# MCU.net
KiCad netlist of a schematic drawn in Altium Designer
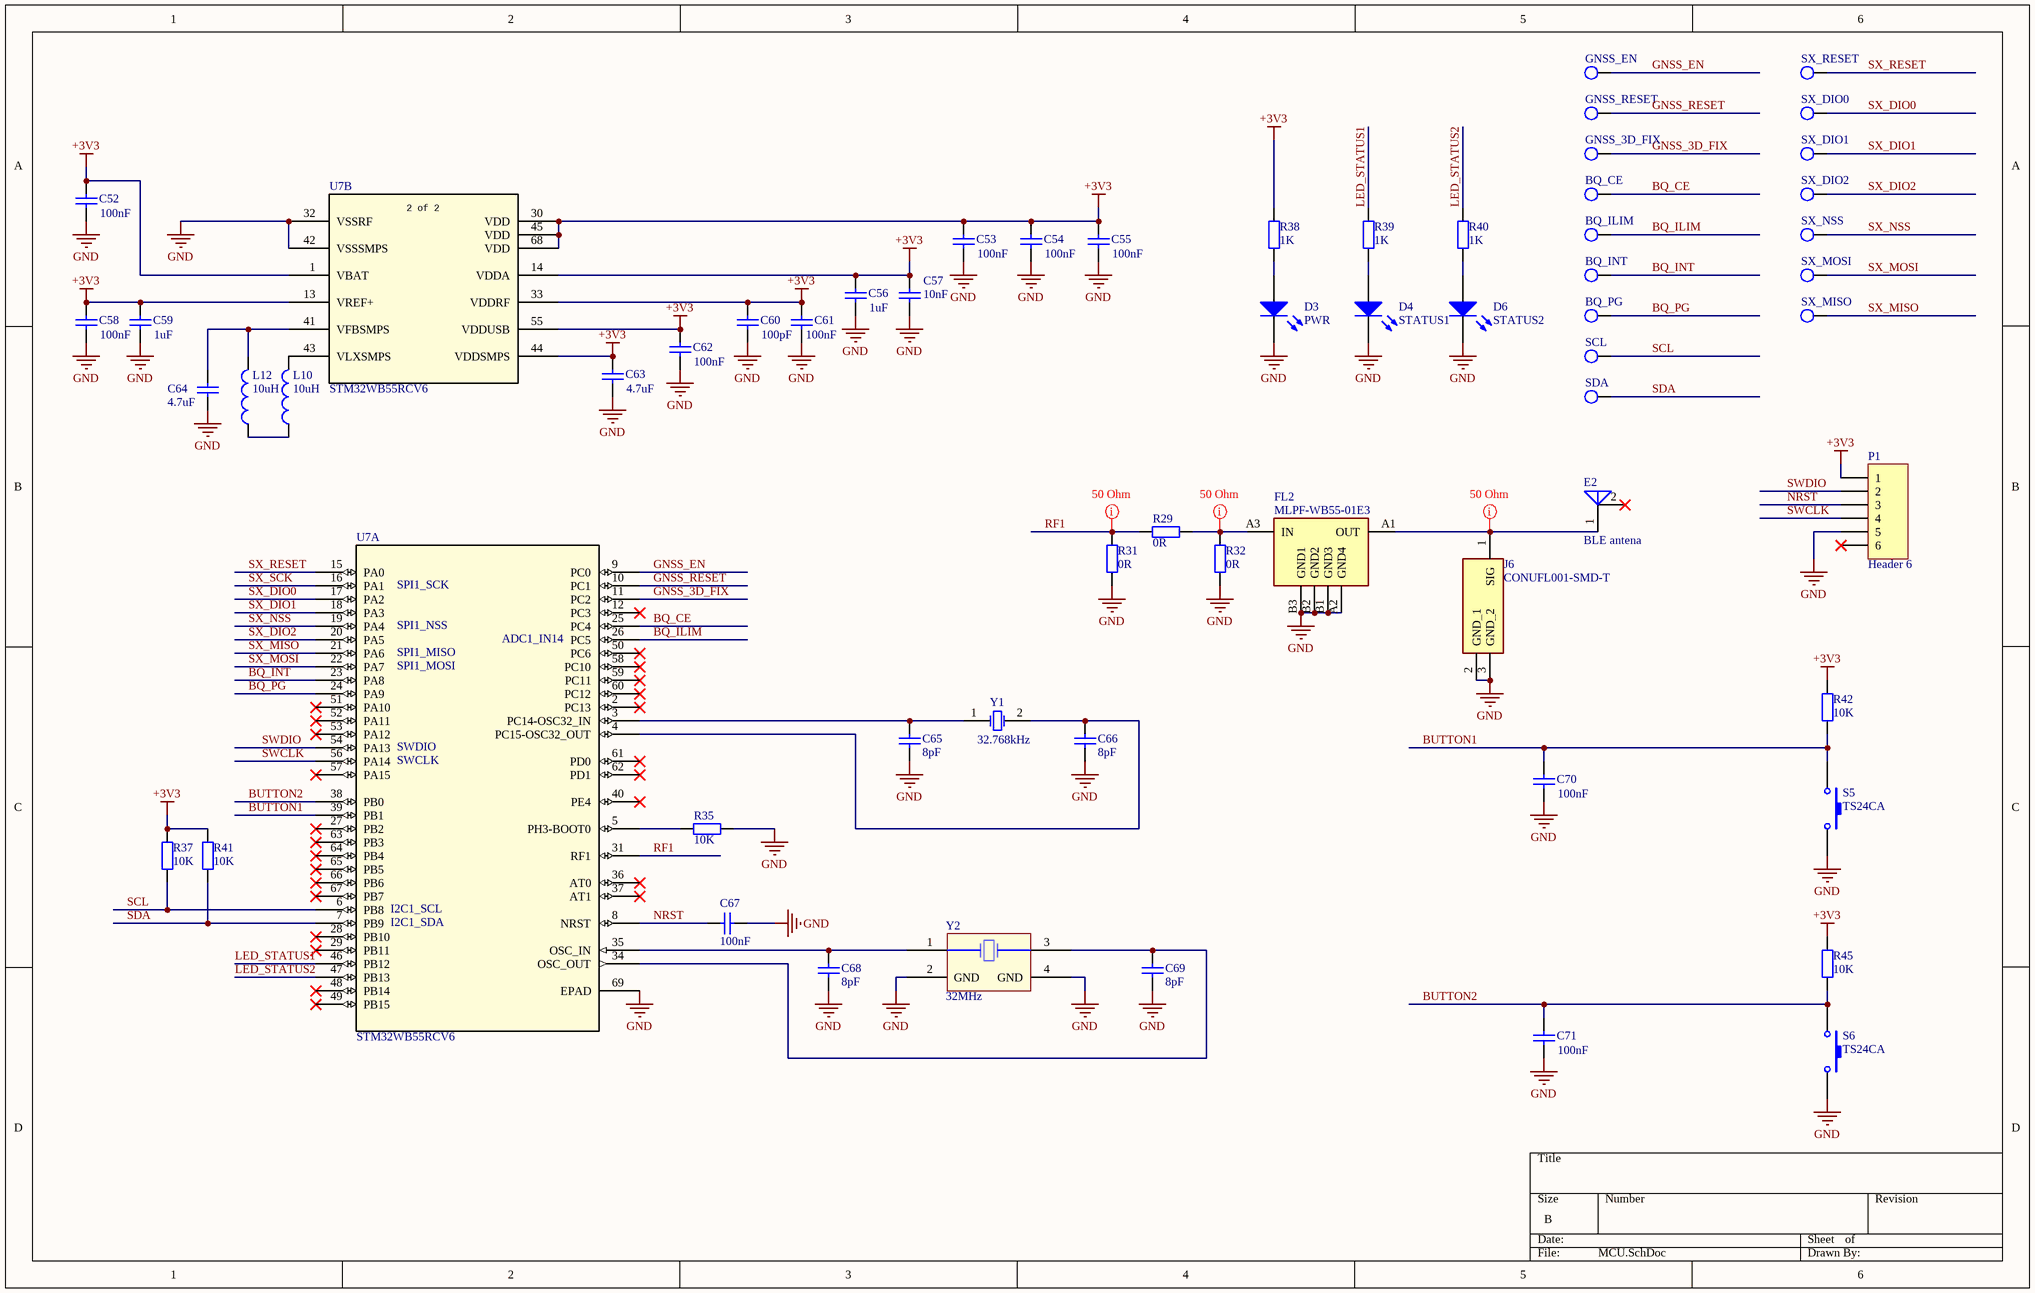
[diagram p0: MCU.SchDoc]

(export (version "E")
  (design (tool "Eeschema 10.0.6"))
  (components
    (comp (ref "BQ_CE")
      (value "BQ_CE")
      (footprint "testpoint 1 mm")
      (libsource (lib "Schematic_library") (part "testpoint"))
    )
    (comp (ref "BQ_ILIM")
      (value "BQ_ILIM")
      (footprint "testpoint 1 mm")
      (libsource (lib "Schematic_library") (part "testpoint"))
    )
    (comp (ref "BQ_INT")
      (value "BQ_INT")
      (footprint "testpoint 1 mm")
      (libsource (lib "Schematic_library") (part "testpoint"))
    )
    (comp (ref "BQ_PG")
      (value "BQ_PG")
      (footprint "testpoint 1 mm")
      (libsource (lib "Schematic_library") (part "testpoint"))
    )
    (comp (ref "C52")
      (value "100nF")
      (footprint "SMD-0402C")
      (description "Capacitor")
      (fields (field (name "PUBLISHER") "Altium Limited"))
      (libsource (lib "Miscellaneous Devices") (part "Cap"))
    )
    (comp (ref "C53")
      (value "100nF")
      (footprint "SMD-0402C")
      (description "Capacitor")
      (fields (field (name "PUBLISHER") "Altium Limited"))
      (libsource (lib "Miscellaneous Devices") (part "Cap"))
    )
    (comp (ref "C54")
      (value "100nF")
      (footprint "SMD-0402C")
      (description "Capacitor")
      (fields (field (name "PUBLISHER") "Altium Limited"))
      (libsource (lib "Miscellaneous Devices") (part "Cap"))
    )
    (comp (ref "C55")
      (value "100nF")
      (footprint "SMD-0402C")
      (description "Capacitor")
      (fields (field (name "PUBLISHER") "Altium Limited"))
      (libsource (lib "Miscellaneous Devices") (part "Cap"))
    )
    (comp (ref "C56")
      (value "1uF")
      (footprint "SMD-0402C")
      (description "Capacitor")
      (fields (field (name "PUBLISHER") "Altium Limited"))
      (libsource (lib "Miscellaneous Devices") (part "Cap"))
    )
    (comp (ref "C57")
      (value "10nF")
      (footprint "SMD-0402C")
      (description "Capacitor")
      (fields (field (name "PUBLISHER") "Altium Limited"))
      (libsource (lib "Miscellaneous Devices") (part "Cap"))
    )
    (comp (ref "C58")
      (value "100nF")
      (footprint "SMD-0402C")
      (description "Capacitor")
      (fields (field (name "PUBLISHER") "Altium Limited"))
      (libsource (lib "Miscellaneous Devices") (part "Cap"))
    )
    (comp (ref "C59")
      (value "1uF")
      (footprint "SMD-0402C")
      (description "Capacitor")
      (fields (field (name "PUBLISHER") "Altium Limited"))
      (libsource (lib "Miscellaneous Devices") (part "Cap"))
    )
    (comp (ref "C60")
      (value "100pF")
      (footprint "SMD-0402C")
      (description "Capacitor")
      (fields (field (name "PUBLISHER") "Altium Limited"))
      (libsource (lib "Miscellaneous Devices") (part "Cap"))
    )
    (comp (ref "C61")
      (value "100nF")
      (footprint "SMD-0402C")
      (description "Capacitor")
      (fields (field (name "PUBLISHER") "Altium Limited"))
      (libsource (lib "Miscellaneous Devices") (part "Cap"))
    )
    (comp (ref "C62")
      (value "100nF")
      (footprint "SMD-0402C")
      (description "Capacitor")
      (fields (field (name "PUBLISHER") "Altium Limited"))
      (libsource (lib "Miscellaneous Devices") (part "Cap"))
    )
    (comp (ref "C63")
      (value "4.7uF")
      (footprint "SMD-0603C")
      (description "Capacitor")
      (fields (field (name "PUBLISHER") "Altium Limited"))
      (libsource (lib "Miscellaneous Devices") (part "Cap"))
    )
    (comp (ref "C64")
      (value "4.7uF")
      (footprint "SMD-0603C")
      (description "Capacitor")
      (fields (field (name "PUBLISHER") "Altium Limited"))
      (libsource (lib "Miscellaneous Devices") (part "Cap"))
    )
    (comp (ref "C65")
      (value "8pF")
      (footprint "SMD-0402C")
      (description "Capacitor")
      (fields (field (name "PUBLISHER") "Altium Limited"))
      (libsource (lib "Miscellaneous Devices") (part "Cap"))
    )
    (comp (ref "C66")
      (value "8pF")
      (footprint "SMD-0402C")
      (description "Capacitor")
      (fields (field (name "PUBLISHER") "Altium Limited"))
      (libsource (lib "Miscellaneous Devices") (part "Cap"))
    )
    (comp (ref "C67")
      (value "100nF")
      (footprint "SMD-0402C")
      (description "Capacitor")
      (fields (field (name "PUBLISHER") "Altium Limited"))
      (libsource (lib "Miscellaneous Devices") (part "Cap"))
    )
    (comp (ref "C68")
      (value "8pF")
      (footprint "SMD-0402C")
      (description "Capacitor")
      (fields (field (name "PUBLISHER") "Altium Limited"))
      (libsource (lib "Miscellaneous Devices") (part "Cap"))
    )
    (comp (ref "C69")
      (value "8pF")
      (footprint "SMD-0402C")
      (description "Capacitor")
      (fields (field (name "PUBLISHER") "Altium Limited"))
      (libsource (lib "Miscellaneous Devices") (part "Cap"))
    )
    (comp (ref "C70")
      (value "100nF")
      (footprint "SMD-0402C")
      (description "Capacitor")
      (fields (field (name "PUBLISHER") "Altium Limited"))
      (libsource (lib "Miscellaneous Devices") (part "Cap"))
    )
    (comp (ref "C71")
      (value "100nF")
      (footprint "SMD-0402C")
      (description "Capacitor")
      (fields (field (name "PUBLISHER") "Altium Limited"))
      (libsource (lib "Miscellaneous Devices") (part "Cap"))
    )
    (comp (ref "D3")
      (value "PWR")
      (footprint "LED 0603")
      (description "Single Colour LEDs SMD Green 2.5-16 mcd")
      (fields (field (name "PUBLISHER") "Altium Limited"))
      (libsource (lib "Miscellaneous Devices") (part "LED1"))
    )
    (comp (ref "D4")
      (value "STATUS1")
      (footprint "LED 0603")
      (description "Single Colour LEDs SMD Green 2.5-16 mcd")
      (fields (field (name "PUBLISHER") "Altium Limited"))
      (libsource (lib "Miscellaneous Devices") (part "LED1"))
    )
    (comp (ref "D6")
      (value "STATUS2")
      (footprint "LED 0603")
      (description "Single Colour LEDs SMD Green 2.5-16 mcd")
      (fields (field (name "PUBLISHER") "Altium Limited"))
      (libsource (lib "Miscellaneous Devices") (part "LED1"))
    )
    (comp (ref "E2")
      (value "BLE antena")
      (footprint "ANT3216LL00R2400A")
      (description "ANT3216LL00R2400A")
      (libsource (lib "Schematic_library") (part "Antenna"))
    )
    (comp (ref "FL2")
      (value "MLPF-WB55-01E3")
      (footprint "MLPF-WB55-01E3")
      (fields (field (name "MOUSER PART NUMBER") "511-MLPF-WB55-01E3"))
      (libsource (lib "Schematic_library") (part "MLPF-WB55-01E3"))
    )
    (comp (ref "GNSS_3D_FIX")
      (value "GNSS_EN")
      (footprint "testpoint 1 mm")
      (libsource (lib "Schematic_library") (part "testpoint"))
    )
    (comp (ref "GNSS_EN")
      (value "GNSS_EN")
      (footprint "testpoint 1 mm")
      (libsource (lib "Schematic_library") (part "testpoint"))
    )
    (comp (ref "GNSS_RESET")
      (value "GNSS_RESET")
      (footprint "testpoint 1 mm")
      (libsource (lib "Schematic_library") (part "testpoint"))
    )
    (comp (ref "J6")
      (value "CONUFL001-SMD-T")
      (footprint "SamacSys:CONUFL001SMDT")
      (description "Connector")
      (libsource (lib "Schematic_library") (part "CONUFL001-SMD-T"))
    )
    (comp (ref "L10")
      (value "10uH")
      (footprint "SMD-0805-RES")
      (description "Inductor")
      (fields (field (name "PUBLISHER") "Altium Limited"))
      (libsource (lib "Miscellaneous Devices") (part "Inductor"))
    )
    (comp (ref "L12")
      (value "10uH")
      (footprint "SMD-0805-RES")
      (description "Inductor")
      (fields (field (name "PUBLISHER") "Altium Limited"))
      (libsource (lib "Miscellaneous Devices") (part "Inductor"))
    )
    (comp (ref "P1")
      (value "Header 6")
      (footprint "TAG_TC2030-IDC-NL")
      (description "Header, 6-Pin")
      (fields (field (name "PUBLISHER") "Altium Limited"))
      (libsource (lib "Miscellaneous Connectors") (part "Header 6"))
    )
    (comp (ref "R29")
      (value "0R")
      (footprint "SMD-0402-RES")
      (description "Resistor")
      (fields (field (name "PUBLISHER") "Altium Limited"))
      (libsource (lib "Miscellaneous Devices") (part "Res2"))
    )
    (comp (ref "R31")
      (value "0R")
      (footprint "SMD-0402-RES")
      (description "Resistor")
      (fields (field (name "PUBLISHER") "Altium Limited"))
      (libsource (lib "") (part "Res2_1"))
    )
    (comp (ref "R32")
      (value "0R")
      (footprint "SMD-0402-RES")
      (description "Resistor")
      (fields (field (name "PUBLISHER") "Altium Limited"))
      (libsource (lib "") (part "Res2_1"))
    )
    (comp (ref "R35")
      (value "10K")
      (footprint "SMD-0402-RES")
      (description "Resistor")
      (fields (field (name "PUBLISHER") "Altium Limited"))
      (libsource (lib "Miscellaneous Devices") (part "Res2"))
    )
    (comp (ref "R37")
      (value "10K")
      (footprint "SMD-0402-RES")
      (description "Resistor")
      (fields (field (name "PUBLISHER") "Altium Limited"))
      (libsource (lib "") (part "Res2_1"))
    )
    (comp (ref "R38")
      (value "1K")
      (footprint "SMD-0402-RES")
      (description "Resistor")
      (fields (field (name "PUBLISHER") "Altium Limited"))
      (libsource (lib "") (part "Res2_2"))
    )
    (comp (ref "R39")
      (value "1K")
      (footprint "SMD-0402-RES")
      (description "Resistor")
      (fields (field (name "PUBLISHER") "Altium Limited"))
      (libsource (lib "") (part "Res2_2"))
    )
    (comp (ref "R40")
      (value "1K")
      (footprint "SMD-0402-RES")
      (description "Resistor")
      (fields (field (name "PUBLISHER") "Altium Limited"))
      (libsource (lib "") (part "Res2_2"))
    )
    (comp (ref "R41")
      (value "10K")
      (footprint "SMD-0402-RES")
      (description "Resistor")
      (fields (field (name "PUBLISHER") "Altium Limited"))
      (libsource (lib "") (part "Res2_1"))
    )
    (comp (ref "R42")
      (value "10K")
      (footprint "SMD-0402-RES")
      (description "Resistor")
      (fields (field (name "PUBLISHER") "Altium Limited"))
      (libsource (lib "") (part "Res2_1"))
    )
    (comp (ref "R45")
      (value "10K")
      (footprint "SMD-0402-RES")
      (description "Resistor")
      (fields (field (name "PUBLISHER") "Altium Limited"))
      (libsource (lib "") (part "Res2_1"))
    )
    (comp (ref "S5")
      (value "TS24CA")
      (footprint "TS24CA")
      (description "Switch")
      (fields (field (name "PUBLISHER") "Altium Limited"))
      (libsource (lib "Miscellaneous Devices") (part "SW-PB"))
    )
    (comp (ref "S6")
      (value "TS24CA")
      (footprint "TS24CA")
      (description "Switch")
      (fields (field (name "PUBLISHER") "Altium Limited"))
      (libsource (lib "Miscellaneous Devices") (part "SW-PB"))
    )
    (comp (ref "SCL")
      (value "SCL")
      (footprint "testpoint 1 mm")
      (libsource (lib "Schematic_library") (part "testpoint"))
    )
    (comp (ref "SDA")
      (value "SDA")
      (footprint "testpoint 1 mm")
      (libsource (lib "Schematic_library") (part "testpoint"))
    )
    (comp (ref "SX_DIO0")
      (value "SX_DIO0")
      (footprint "testpoint 1 mm")
      (libsource (lib "Schematic_library") (part "testpoint"))
    )
    (comp (ref "SX_DIO1")
      (value "SX_DIO1")
      (footprint "testpoint 1 mm")
      (libsource (lib "Schematic_library") (part "testpoint"))
    )
    (comp (ref "SX_DIO2")
      (value "SX_DIO2")
      (footprint "testpoint 1 mm")
      (libsource (lib "Schematic_library") (part "testpoint"))
    )
    (comp (ref "SX_MISO")
      (value "SX_MISO")
      (footprint "testpoint 1 mm")
      (libsource (lib "Schematic_library") (part "testpoint"))
    )
    (comp (ref "SX_MOSI")
      (value "SX_MOSI")
      (footprint "testpoint 1 mm")
      (libsource (lib "Schematic_library") (part "testpoint"))
    )
    (comp (ref "SX_NSS")
      (value "SX_NSS")
      (footprint "testpoint 1 mm")
      (libsource (lib "Schematic_library") (part "testpoint"))
    )
    (comp (ref "SX_RESET")
      (value "SX_RESET")
      (footprint "testpoint 1 mm")
      (libsource (lib "Schematic_library") (part "testpoint"))
    )
    (comp (ref "U7")
      (value "STM32WB55RCV6")
      (footprint "STM32WB55RCV6")
      (fields (field (name "COPYRIGHT") "Copyright (C) 2025 Ultra Librarian. All rights reserved."))
      (libsource (lib "Schematic_library") (part "STM32WB55RCV6"))
    )
    (comp (ref "Y1")
      (value "32.768kHz")
      (footprint "DT1610SB32768B0HPWAA")
      (description "Crystal Oscillator\r\nCM8V-T1A-32.768kHz-7pF-20PPM-TA-QC")
      (fields (field (name "PUBLISHER") "Altium Limited"))
      (libsource (lib "Miscellaneous Devices") (part "XTAL"))
    )
    (comp (ref "Y2")
      (value "32MHz")
      (footprint "ECS-TXO-20CSMV-320-EY-TR")
      (libsource (lib "Schematic_library") (part "Xtal 4 pin"))
    )
  )
  (nets
    (net (code "1") (name "+3V3") (class "Default")
      (node (ref "C52") (pin "2") (pinfunction "2_2") (pintype "passive"))
      (node (ref "C53") (pin "2") (pinfunction "2_2") (pintype "passive"))
      (node (ref "C54") (pin "2") (pinfunction "2_2") (pintype "passive"))
      (node (ref "C55") (pin "2") (pinfunction "2_2") (pintype "passive"))
      (node (ref "C56") (pin "2") (pinfunction "2_2") (pintype "passive"))
      (node (ref "C57") (pin "2") (pinfunction "2_2") (pintype "passive"))
      (node (ref "C58") (pin "2") (pinfunction "2_2") (pintype "passive"))
      (node (ref "C59") (pin "2") (pinfunction "2_2") (pintype "passive"))
      (node (ref "C60") (pin "2") (pinfunction "2_2") (pintype "passive"))
      (node (ref "C61") (pin "2") (pinfunction "2_2") (pintype "passive"))
      (node (ref "C62") (pin "2") (pinfunction "2_2") (pintype "passive"))
      (node (ref "C63") (pin "2") (pinfunction "2_2") (pintype "passive"))
      (node (ref "P1") (pin "1") (pinfunction "1_1") (pintype "passive"))
      (node (ref "R37") (pin "2") (pinfunction "2_2") (pintype "passive"))
      (node (ref "R38") (pin "1") (pinfunction "1_1") (pintype "passive"))
      (node (ref "R41") (pin "2") (pinfunction "2_2") (pintype "passive"))
      (node (ref "R42") (pin "2") (pinfunction "2_2") (pintype "passive"))
      (node (ref "R45") (pin "2") (pinfunction "2_2") (pintype "passive"))
      (node (ref "U7") (pin "1") (pinfunction "VBAT_1") (pintype "power_in"))
      (node (ref "U7") (pin "13") (pinfunction "VREF+_13") (pintype "power_in"))
      (node (ref "U7") (pin "14") (pinfunction "VDDA_14") (pintype "power_in"))
      (node (ref "U7") (pin "30") (pinfunction "VDD_30") (pintype "power_in"))
      (node (ref "U7") (pin "33") (pinfunction "VDDRF_33") (pintype "power_in"))
      (node (ref "U7") (pin "44") (pinfunction "VDDSMPS_44") (pintype "power_in"))
      (node (ref "U7") (pin "45") (pinfunction "VDD_45") (pintype "power_in"))
      (node (ref "U7") (pin "55") (pinfunction "VDDUSB_55") (pintype "power_in"))
      (node (ref "U7") (pin "68") (pinfunction "VDD_68") (pintype "power_in"))
    )
    (net (code "2") (name "/BQ_CE") (class "Default")
      (node (ref "BQ_CE") (pin "1") (pinfunction "1_1") (pintype "passive"))
      (node (ref "U7") (pin "25") (pinfunction "PC4_25") (pintype "bidirectional"))
    )
    (net (code "3") (name "/BQ_ILIM") (class "Default")
      (node (ref "BQ_ILIM") (pin "1") (pinfunction "1_1") (pintype "passive"))
      (node (ref "U7") (pin "26") (pinfunction "PC5_26") (pintype "bidirectional"))
    )
    (net (code "4") (name "/BQ_INT") (class "Default")
      (node (ref "BQ_INT") (pin "1") (pinfunction "1_1") (pintype "passive"))
      (node (ref "U7") (pin "23") (pinfunction "PA8_23") (pintype "bidirectional"))
    )
    (net (code "5") (name "/BQ_PG") (class "Default")
      (node (ref "BQ_PG") (pin "1") (pinfunction "1_1") (pintype "passive"))
      (node (ref "U7") (pin "24") (pinfunction "PA9_24") (pintype "bidirectional"))
    )
    (net (code "6") (name "/BUTTON1") (class "Default")
      (node (ref "C70") (pin "2") (pinfunction "2_2") (pintype "passive"))
      (node (ref "R42") (pin "1") (pinfunction "1_1") (pintype "passive"))
      (node (ref "S5") (pin "1") (pinfunction "1_1") (pintype "passive"))
      (node (ref "U7") (pin "39") (pinfunction "PB1_39") (pintype "bidirectional"))
    )
    (net (code "7") (name "/BUTTON2") (class "Default")
      (node (ref "C71") (pin "2") (pinfunction "2_2") (pintype "passive"))
      (node (ref "R45") (pin "1") (pinfunction "1_1") (pintype "passive"))
      (node (ref "S6") (pin "1") (pinfunction "1_1") (pintype "passive"))
      (node (ref "U7") (pin "38") (pinfunction "PB0_38") (pintype "bidirectional"))
    )
    (net (code "8") (name "/GNSS_3D_FIX") (class "Default")
      (node (ref "GNSS_3D_FIX") (pin "1") (pinfunction "1_1") (pintype "passive"))
      (node (ref "U7") (pin "11") (pinfunction "PC2_11") (pintype "bidirectional"))
    )
    (net (code "9") (name "/GNSS_EN") (class "Default")
      (node (ref "GNSS_EN") (pin "1") (pinfunction "1_1") (pintype "passive"))
      (node (ref "U7") (pin "9") (pinfunction "PC0_9") (pintype "bidirectional"))
    )
    (net (code "10") (name "/GNSS_RESET") (class "Default")
      (node (ref "GNSS_RESET") (pin "1") (pinfunction "1_1") (pintype "passive"))
      (node (ref "U7") (pin "10") (pinfunction "PC1_10") (pintype "bidirectional"))
    )
    (net (code "11") (name "/LED_STATUS1") (class "Default")
      (node (ref "R39") (pin "1") (pinfunction "1_1") (pintype "passive"))
      (node (ref "U7") (pin "46") (pinfunction "PB12_46") (pintype "bidirectional"))
    )
    (net (code "12") (name "/LED_STATUS2") (class "Default")
      (node (ref "R40") (pin "1") (pinfunction "1_1") (pintype "passive"))
      (node (ref "U7") (pin "47") (pinfunction "PB13_47") (pintype "bidirectional"))
    )
    (net (code "13") (name "/NRST") (class "Default")
      (node (ref "C67") (pin "2") (pinfunction "2_2") (pintype "passive"))
      (node (ref "P1") (pin "3") (pinfunction "3_3") (pintype "passive"))
      (node (ref "U7") (pin "8") (pinfunction "NRST_8") (pintype "bidirectional"))
    )
    (net (code "14") (name "/RF1") (class "Default")
      (node (ref "R29") (pin "2") (pinfunction "2_2") (pintype "passive"))
      (node (ref "R31") (pin "2") (pinfunction "2_2") (pintype "passive"))
      (node (ref "U7") (pin "31") (pinfunction "RF1_31") (pintype "bidirectional"))
    )
    (net (code "15") (name "/SCL") (class "Default")
      (node (ref "R37") (pin "1") (pinfunction "1_1") (pintype "passive"))
      (node (ref "SCL") (pin "1") (pinfunction "1_1") (pintype "passive"))
      (node (ref "U7") (pin "6") (pinfunction "PB8_6") (pintype "bidirectional"))
    )
    (net (code "16") (name "/SDA") (class "Default")
      (node (ref "R41") (pin "1") (pinfunction "1_1") (pintype "passive"))
      (node (ref "SDA") (pin "1") (pinfunction "1_1") (pintype "passive"))
      (node (ref "U7") (pin "7") (pinfunction "PB9_7") (pintype "bidirectional"))
    )
    (net (code "17") (name "/SWCLK") (class "Default")
      (node (ref "P1") (pin "4") (pinfunction "4_4") (pintype "passive"))
      (node (ref "U7") (pin "56") (pinfunction "PA14_56") (pintype "bidirectional"))
    )
    (net (code "18") (name "/SWDIO") (class "Default")
      (node (ref "P1") (pin "2") (pinfunction "2_2") (pintype "passive"))
      (node (ref "U7") (pin "54") (pinfunction "PA13_54") (pintype "bidirectional"))
    )
    (net (code "19") (name "/SX_DIO0") (class "Default")
      (node (ref "SX_DIO0") (pin "1") (pinfunction "1_1") (pintype "passive"))
      (node (ref "U7") (pin "17") (pinfunction "PA2_17") (pintype "bidirectional"))
    )
    (net (code "20") (name "/SX_DIO1") (class "Default")
      (node (ref "SX_DIO1") (pin "1") (pinfunction "1_1") (pintype "passive"))
      (node (ref "U7") (pin "18") (pinfunction "PA3_18") (pintype "bidirectional"))
    )
    (net (code "21") (name "/SX_DIO2") (class "Default")
      (node (ref "SX_DIO2") (pin "1") (pinfunction "1_1") (pintype "passive"))
      (node (ref "U7") (pin "20") (pinfunction "PA5_20") (pintype "bidirectional"))
    )
    (net (code "22") (name "/SX_MISO") (class "Default")
      (node (ref "SX_MISO") (pin "1") (pinfunction "1_1") (pintype "passive"))
      (node (ref "U7") (pin "21") (pinfunction "PA6_21") (pintype "bidirectional"))
    )
    (net (code "23") (name "/SX_MOSI") (class "Default")
      (node (ref "SX_MOSI") (pin "1") (pinfunction "1_1") (pintype "passive"))
      (node (ref "U7") (pin "22") (pinfunction "PA7_22") (pintype "bidirectional"))
    )
    (net (code "24") (name "/SX_NSS") (class "Default")
      (node (ref "SX_NSS") (pin "1") (pinfunction "1_1") (pintype "passive"))
      (node (ref "U7") (pin "19") (pinfunction "PA4_19") (pintype "bidirectional"))
    )
    (net (code "25") (name "/SX_RESET") (class "Default")
      (node (ref "SX_RESET") (pin "1") (pinfunction "1_1") (pintype "passive"))
      (node (ref "U7") (pin "15") (pinfunction "PA0_15") (pintype "bidirectional"))
    )
    (net (code "26") (name "/SX_SCK") (class "Default")
      (node (ref "U7") (pin "16") (pinfunction "PA1_16") (pintype "bidirectional"))
    )
    (net (code "27") (name "GND") (class "Default")
      (node (ref "C52") (pin "1") (pinfunction "1_1") (pintype "passive"))
      (node (ref "C53") (pin "1") (pinfunction "1_1") (pintype "passive"))
      (node (ref "C54") (pin "1") (pinfunction "1_1") (pintype "passive"))
      (node (ref "C55") (pin "1") (pinfunction "1_1") (pintype "passive"))
      (node (ref "C56") (pin "1") (pinfunction "1_1") (pintype "passive"))
      (node (ref "C57") (pin "1") (pinfunction "1_1") (pintype "passive"))
      (node (ref "C58") (pin "1") (pinfunction "1_1") (pintype "passive"))
      (node (ref "C59") (pin "1") (pinfunction "1_1") (pintype "passive"))
      (node (ref "C60") (pin "1") (pinfunction "1_1") (pintype "passive"))
      (node (ref "C61") (pin "1") (pinfunction "1_1") (pintype "passive"))
      (node (ref "C62") (pin "1") (pinfunction "1_1") (pintype "passive"))
      (node (ref "C63") (pin "1") (pinfunction "1_1") (pintype "passive"))
      (node (ref "C64") (pin "1") (pinfunction "1_1") (pintype "passive"))
      (node (ref "C65") (pin "2") (pinfunction "2_2") (pintype "passive"))
      (node (ref "C66") (pin "2") (pinfunction "2_2") (pintype "passive"))
      (node (ref "C67") (pin "1") (pinfunction "1_1") (pintype "passive"))
      (node (ref "C68") (pin "2") (pinfunction "2_2") (pintype "passive"))
      (node (ref "C69") (pin "2") (pinfunction "2_2") (pintype "passive"))
      (node (ref "C70") (pin "1") (pinfunction "1_1") (pintype "passive"))
      (node (ref "C71") (pin "1") (pinfunction "1_1") (pintype "passive"))
      (node (ref "D3") (pin "2") (pinfunction "K_2") (pintype "passive"))
      (node (ref "D4") (pin "2") (pinfunction "K_2") (pintype "passive"))
      (node (ref "D6") (pin "2") (pinfunction "K_2") (pintype "passive"))
      (node (ref "FL2") (pin "A2") (pinfunction "GND4_A2") (pintype "passive"))
      (node (ref "FL2") (pin "B1") (pinfunction "GND3_B1") (pintype "passive"))
      (node (ref "FL2") (pin "B2") (pinfunction "GND2_B2") (pintype "passive"))
      (node (ref "FL2") (pin "B3") (pinfunction "GND1_B3") (pintype "passive"))
      (node (ref "J6") (pin "2") (pinfunction "GND_1_2") (pintype "passive"))
      (node (ref "J6") (pin "3") (pinfunction "GND_2_3") (pintype "passive"))
      (node (ref "P1") (pin "5") (pinfunction "5_5") (pintype "passive"))
      (node (ref "R31") (pin "1") (pinfunction "1_1") (pintype "passive"))
      (node (ref "R32") (pin "1") (pinfunction "1_1") (pintype "passive"))
      (node (ref "R35") (pin "1") (pinfunction "1_1") (pintype "passive"))
      (node (ref "S5") (pin "2") (pinfunction "2_2") (pintype "passive"))
      (node (ref "S6") (pin "2") (pinfunction "2_2") (pintype "passive"))
      (node (ref "U7") (pin "32") (pinfunction "VSSRF_32") (pintype "power_in"))
      (node (ref "U7") (pin "42") (pinfunction "VSSSMPS_42") (pintype "power_in"))
      (node (ref "U7") (pin "69") (pinfunction "EPAD_69") (pintype "passive"))
      (node (ref "Y2") (pin "2") (pinfunction "GND_2") (pintype "passive"))
      (node (ref "Y2") (pin "4") (pinfunction "GND_4") (pintype "passive"))
    )
    (net (code "28") (name "Net-(D3-A)") (class "Default")
      (node (ref "D3") (pin "1") (pinfunction "A_1") (pintype "passive"))
      (node (ref "R38") (pin "2") (pinfunction "2_2") (pintype "passive"))
    )
    (net (code "29") (name "Net-(D4-A)") (class "Default")
      (node (ref "D4") (pin "1") (pinfunction "A_1") (pintype "passive"))
      (node (ref "R39") (pin "2") (pinfunction "2_2") (pintype "passive"))
    )
    (net (code "30") (name "Net-(D6-A)") (class "Default")
      (node (ref "D6") (pin "1") (pinfunction "A_1") (pintype "passive"))
      (node (ref "R40") (pin "2") (pinfunction "2_2") (pintype "passive"))
    )
    (net (code "31") (name "Net-(FL2-IN)") (class "Default")
      (node (ref "FL2") (pin "A3") (pinfunction "IN_A3") (pintype "passive"))
      (node (ref "R29") (pin "1") (pinfunction "1_1") (pintype "passive"))
      (node (ref "R32") (pin "2") (pinfunction "2_2") (pintype "passive"))
    )
    (net (code "32") (name "Net-(FL2-OUT)") (class "Default")
      (node (ref "E2") (pin "1") (pinfunction "1_1") (pintype "passive"))
      (node (ref "FL2") (pin "A1") (pinfunction "OUT_A1") (pintype "passive"))
      (node (ref "J6") (pin "1") (pinfunction "SIG_1") (pintype "passive"))
    )
    (net (code "33") (name "Net-(L10-Pad1)") (class "Default")
      (node (ref "L10") (pin "1") (pinfunction "1_1") (pintype "passive"))
      (node (ref "L12") (pin "1") (pinfunction "1_1") (pintype "passive"))
    )
    (net (code "34") (name "Net-(U7A-OSC_IN)") (class "Default")
      (node (ref "C68") (pin "1") (pinfunction "1_1") (pintype "passive"))
      (node (ref "U7") (pin "35") (pinfunction "OSC_IN_35") (pintype "input"))
      (node (ref "Y2") (pin "1") (pinfunction "1_1") (pintype "passive"))
    )
    (net (code "35") (name "Net-(U7A-OSC_OUT)") (class "Default")
      (node (ref "C69") (pin "1") (pinfunction "1_1") (pintype "passive"))
      (node (ref "U7") (pin "34") (pinfunction "OSC_OUT_34") (pintype "output"))
      (node (ref "Y2") (pin "3") (pinfunction "3_3") (pintype "passive"))
    )
    (net (code "36") (name "Net-(U7A-PC14-OSC32_IN)") (class "Default")
      (node (ref "C65") (pin "1") (pinfunction "1_1") (pintype "passive"))
      (node (ref "U7") (pin "3") (pinfunction "PC14-OSC32_IN_3") (pintype "bidirectional"))
      (node (ref "Y1") (pin "1") (pinfunction "OSC1_1") (pintype "passive"))
    )
    (net (code "37") (name "Net-(U7A-PC15-OSC32_OUT)") (class "Default")
      (node (ref "C66") (pin "1") (pinfunction "1_1") (pintype "passive"))
      (node (ref "U7") (pin "4") (pinfunction "PC15-OSC32_OUT_4") (pintype "bidirectional"))
      (node (ref "Y1") (pin "2") (pinfunction "OSC2_2") (pintype "passive"))
    )
    (net (code "38") (name "Net-(U7A-PH3-BOOT0)") (class "Default")
      (node (ref "R35") (pin "2") (pinfunction "2_2") (pintype "passive"))
      (node (ref "U7") (pin "5") (pinfunction "PH3-BOOT0_5") (pintype "bidirectional"))
    )
    (net (code "39") (name "Net-(U7B-VFBSMPS)") (class "Default")
      (node (ref "C64") (pin "2") (pinfunction "2_2") (pintype "passive"))
      (node (ref "L12") (pin "2") (pinfunction "2_2") (pintype "passive"))
      (node (ref "U7") (pin "41") (pinfunction "VFBSMPS_41") (pintype "power_in"))
    )
    (net (code "40") (name "Net-(U7B-VLXSMPS)") (class "Default")
      (node (ref "L10") (pin "2") (pinfunction "2_2") (pintype "passive"))
      (node (ref "U7") (pin "43") (pinfunction "VLXSMPS_43") (pintype "power_in"))
    )
    (net (code "41") (name "unconnected-(E2-Pad2)") (class "Default")
      (node (ref "E2") (pin "2") (pinfunction "2_2") (pintype "passive+no_connect"))
    )
    (net (code "42") (name "unconnected-(P1-Pad6)") (class "Default")
      (node (ref "P1") (pin "6") (pinfunction "6_6") (pintype "passive+no_connect"))
    )
    (net (code "43") (name "unconnected-(U7A-AT0-Pad36)") (class "Default")
      (node (ref "U7") (pin "36") (pinfunction "AT0_36") (pintype "bidirectional+no_connect"))
    )
    (net (code "44") (name "unconnected-(U7A-AT1-Pad37)") (class "Default")
      (node (ref "U7") (pin "37") (pinfunction "AT1_37") (pintype "bidirectional+no_connect"))
    )
    (net (code "45") (name "unconnected-(U7A-PA10-Pad51)") (class "Default")
      (node (ref "U7") (pin "51") (pinfunction "PA10_51") (pintype "bidirectional+no_connect"))
    )
    (net (code "46") (name "unconnected-(U7A-PA11-Pad52)") (class "Default")
      (node (ref "U7") (pin "52") (pinfunction "PA11_52") (pintype "bidirectional+no_connect"))
    )
    (net (code "47") (name "unconnected-(U7A-PA12-Pad53)") (class "Default")
      (node (ref "U7") (pin "53") (pinfunction "PA12_53") (pintype "bidirectional+no_connect"))
    )
    (net (code "48") (name "unconnected-(U7A-PA15-Pad57)") (class "Default")
      (node (ref "U7") (pin "57") (pinfunction "PA15_57") (pintype "bidirectional+no_connect"))
    )
    (net (code "49") (name "unconnected-(U7A-PB2-Pad27)") (class "Default")
      (node (ref "U7") (pin "27") (pinfunction "PB2_27") (pintype "bidirectional+no_connect"))
    )
    (net (code "50") (name "unconnected-(U7A-PB3-Pad63)") (class "Default")
      (node (ref "U7") (pin "63") (pinfunction "PB3_63") (pintype "bidirectional+no_connect"))
    )
    (net (code "51") (name "unconnected-(U7A-PB4-Pad64)") (class "Default")
      (node (ref "U7") (pin "64") (pinfunction "PB4_64") (pintype "bidirectional+no_connect"))
    )
    (net (code "52") (name "unconnected-(U7A-PB5-Pad65)") (class "Default")
      (node (ref "U7") (pin "65") (pinfunction "PB5_65") (pintype "bidirectional+no_connect"))
    )
    (net (code "53") (name "unconnected-(U7A-PB6-Pad66)") (class "Default")
      (node (ref "U7") (pin "66") (pinfunction "PB6_66") (pintype "bidirectional+no_connect"))
    )
    (net (code "54") (name "unconnected-(U7A-PB7-Pad67)") (class "Default")
      (node (ref "U7") (pin "67") (pinfunction "PB7_67") (pintype "bidirectional+no_connect"))
    )
    (net (code "55") (name "unconnected-(U7A-PB10-Pad28)") (class "Default")
      (node (ref "U7") (pin "28") (pinfunction "PB10_28") (pintype "bidirectional+no_connect"))
    )
    (net (code "56") (name "unconnected-(U7A-PB11-Pad29)") (class "Default")
      (node (ref "U7") (pin "29") (pinfunction "PB11_29") (pintype "bidirectional+no_connect"))
    )
    (net (code "57") (name "unconnected-(U7A-PB14-Pad48)") (class "Default")
      (node (ref "U7") (pin "48") (pinfunction "PB14_48") (pintype "bidirectional+no_connect"))
    )
    (net (code "58") (name "unconnected-(U7A-PB15-Pad49)") (class "Default")
      (node (ref "U7") (pin "49") (pinfunction "PB15_49") (pintype "bidirectional+no_connect"))
    )
    (net (code "59") (name "unconnected-(U7A-PC3-Pad12)") (class "Default")
      (node (ref "U7") (pin "12") (pinfunction "PC3_12") (pintype "bidirectional+no_connect"))
    )
    (net (code "60") (name "unconnected-(U7A-PC6-Pad50)") (class "Default")
      (node (ref "U7") (pin "50") (pinfunction "PC6_50") (pintype "bidirectional+no_connect"))
    )
    (net (code "61") (name "unconnected-(U7A-PC10-Pad58)") (class "Default")
      (node (ref "U7") (pin "58") (pinfunction "PC10_58") (pintype "bidirectional+no_connect"))
    )
    (net (code "62") (name "unconnected-(U7A-PC11-Pad59)") (class "Default")
      (node (ref "U7") (pin "59") (pinfunction "PC11_59") (pintype "bidirectional+no_connect"))
    )
    (net (code "63") (name "unconnected-(U7A-PC12-Pad60)") (class "Default")
      (node (ref "U7") (pin "60") (pinfunction "PC12_60") (pintype "bidirectional+no_connect"))
    )
    (net (code "64") (name "unconnected-(U7A-PC13-Pad2)") (class "Default")
      (node (ref "U7") (pin "2") (pinfunction "PC13_2") (pintype "bidirectional+no_connect"))
    )
    (net (code "65") (name "unconnected-(U7A-PD0-Pad61)") (class "Default")
      (node (ref "U7") (pin "61") (pinfunction "PD0_61") (pintype "bidirectional+no_connect"))
    )
    (net (code "66") (name "unconnected-(U7A-PD1-Pad62)") (class "Default")
      (node (ref "U7") (pin "62") (pinfunction "PD1_62") (pintype "bidirectional+no_connect"))
    )
    (net (code "67") (name "unconnected-(U7A-PE4-Pad40)") (class "Default")
      (node (ref "U7") (pin "40") (pinfunction "PE4_40") (pintype "bidirectional+no_connect"))
    )
  )
)
